# S284X.net
KiCad netlist of a schematic drawn in EAGLE
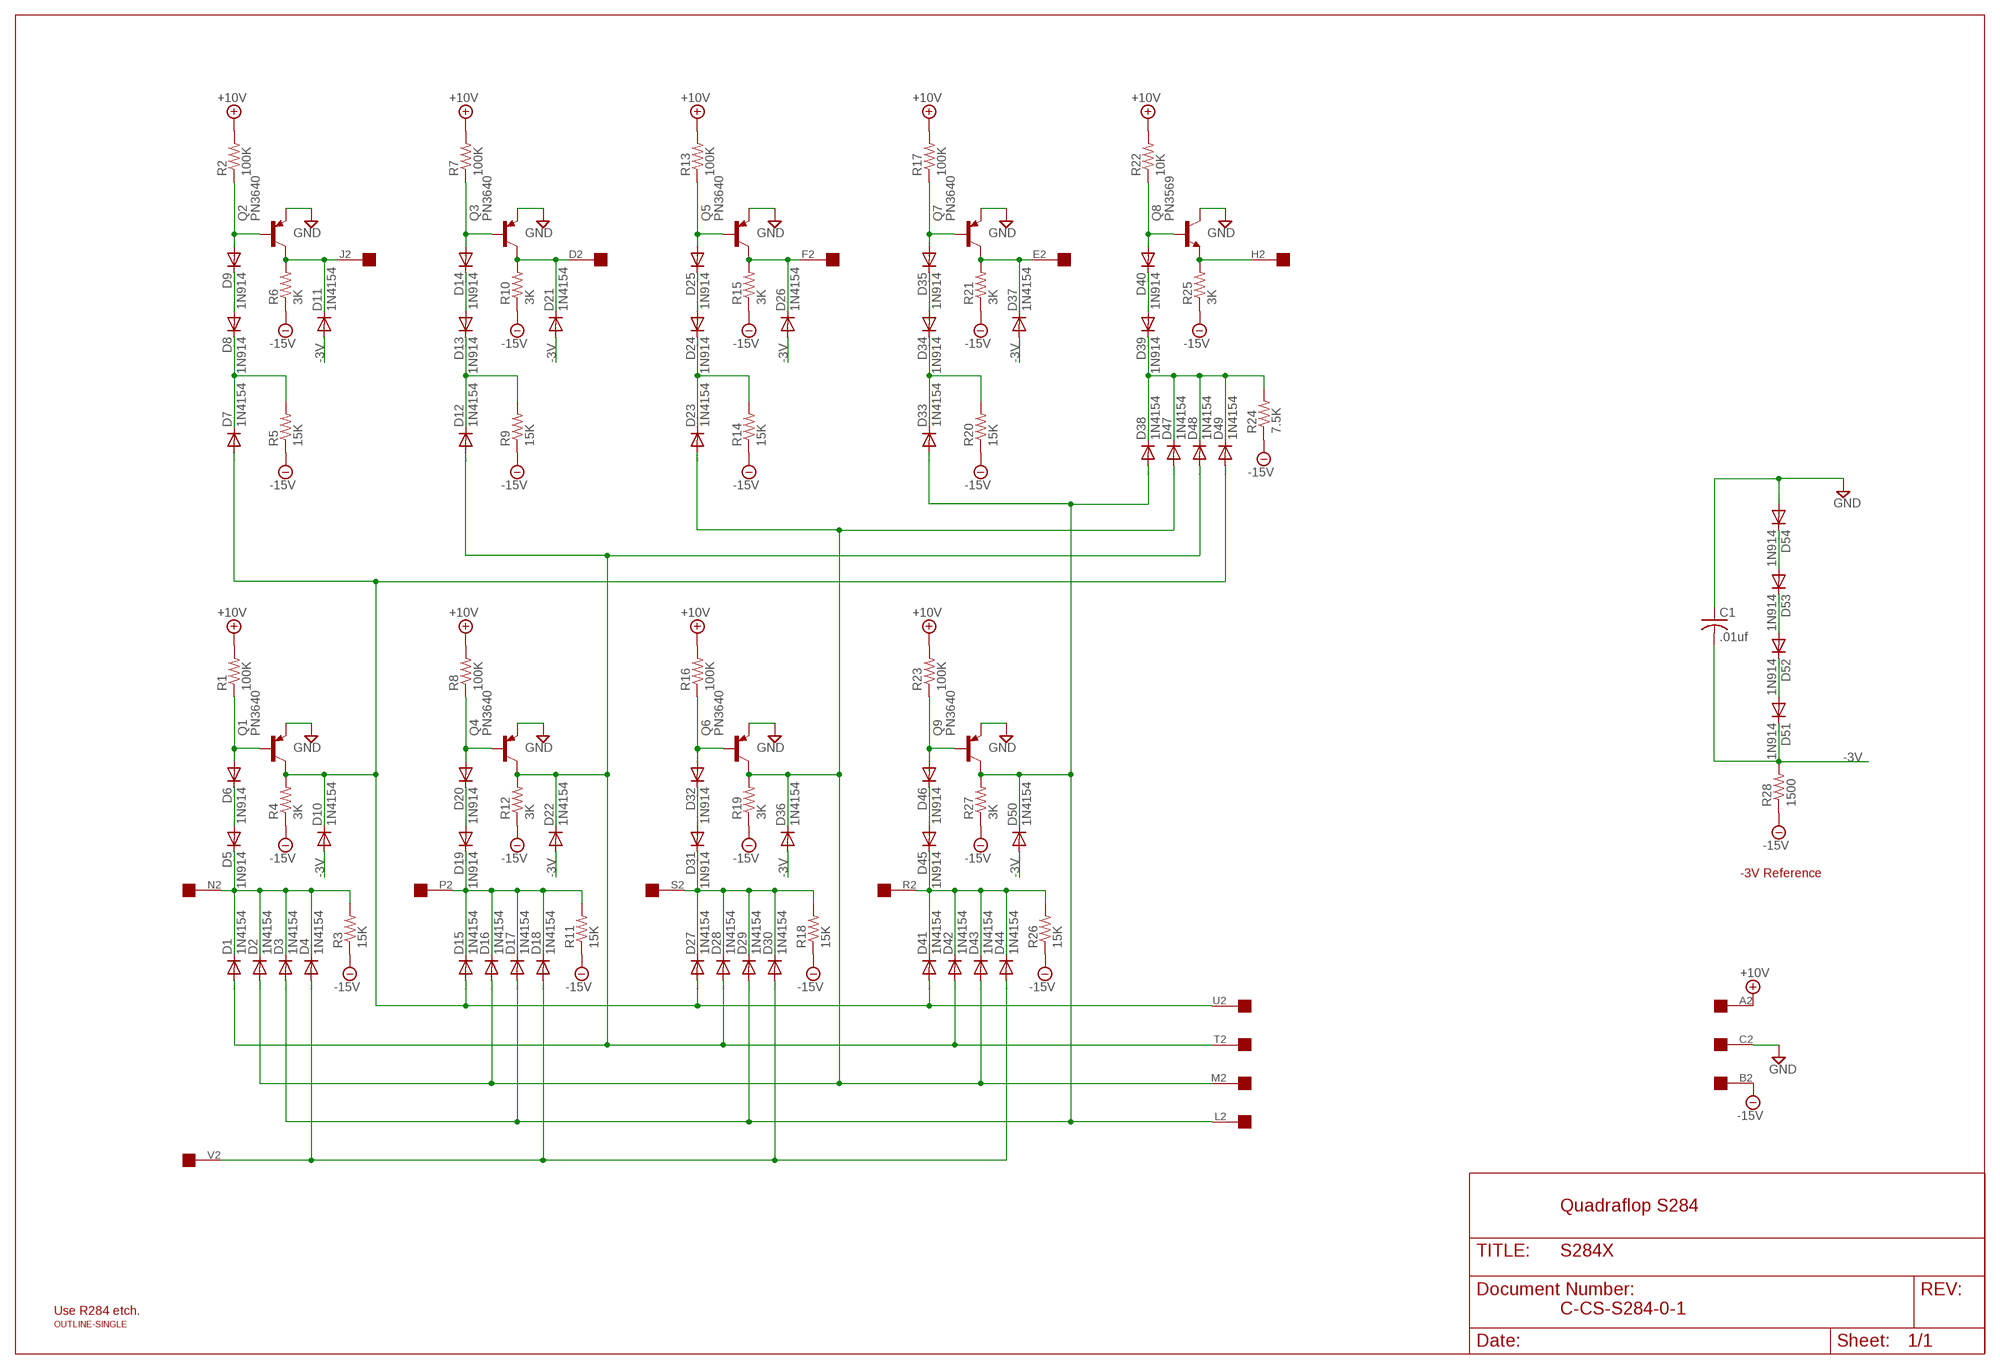
[diagram p0: schematic, sheet 1]

(export (version "E")
  (design (tool "Eeschema 10.0.6"))
  (components
    (comp (ref "C1")
      (value ".01uf")
      (footprint "eagle-import:C050-025X075")
      (libsource (lib "eagle-import") (part "C-US050-025X075"))
    )
    (comp (ref "D1")
      (value "1N4154")
      (footprint "eagle-import:DO35-10")
      (libsource (lib "eagle-import") (part "1N4148DO35-10"))
    )
    (comp (ref "D2")
      (value "1N4154")
      (footprint "eagle-import:DO35-10")
      (libsource (lib "eagle-import") (part "1N4148DO35-10"))
    )
    (comp (ref "D3")
      (value "1N4154")
      (footprint "eagle-import:DO35-10")
      (libsource (lib "eagle-import") (part "1N4148DO35-10"))
    )
    (comp (ref "D4")
      (value "1N4154")
      (footprint "eagle-import:DO35-10")
      (libsource (lib "eagle-import") (part "1N4148DO35-10"))
    )
    (comp (ref "D5")
      (value "1N914")
      (footprint "eagle-import:DO35-10")
      (libsource (lib "eagle-import") (part "1N4148DO35-10"))
    )
    (comp (ref "D6")
      (value "1N914")
      (footprint "eagle-import:DO35-10")
      (libsource (lib "eagle-import") (part "1N4148DO35-10"))
    )
    (comp (ref "D7")
      (value "1N4154")
      (footprint "eagle-import:DO35-10")
      (libsource (lib "eagle-import") (part "1N4148DO35-10"))
    )
    (comp (ref "D8")
      (value "1N914")
      (footprint "eagle-import:DO35-10")
      (libsource (lib "eagle-import") (part "1N4148DO35-10"))
    )
    (comp (ref "D9")
      (value "1N914")
      (footprint "eagle-import:DO35-10")
      (libsource (lib "eagle-import") (part "1N4148DO35-10"))
    )
    (comp (ref "D10")
      (value "1N4154")
      (footprint "eagle-import:DO35-10")
      (libsource (lib "eagle-import") (part "1N4148DO35-10"))
    )
    (comp (ref "D11")
      (value "1N4154")
      (footprint "eagle-import:DO35-10")
      (libsource (lib "eagle-import") (part "1N4148DO35-10"))
    )
    (comp (ref "D12")
      (value "1N4154")
      (footprint "eagle-import:DO35-10")
      (libsource (lib "eagle-import") (part "1N4148DO35-10"))
    )
    (comp (ref "D13")
      (value "1N914")
      (footprint "eagle-import:DO35-10")
      (libsource (lib "eagle-import") (part "1N4148DO35-10"))
    )
    (comp (ref "D14")
      (value "1N914")
      (footprint "eagle-import:DO35-10")
      (libsource (lib "eagle-import") (part "1N4148DO35-10"))
    )
    (comp (ref "D15")
      (value "1N4154")
      (footprint "eagle-import:DO35-10")
      (libsource (lib "eagle-import") (part "1N4148DO35-10"))
    )
    (comp (ref "D16")
      (value "1N4154")
      (footprint "eagle-import:DO35-10")
      (libsource (lib "eagle-import") (part "1N4148DO35-10"))
    )
    (comp (ref "D17")
      (value "1N4154")
      (footprint "eagle-import:DO35-10")
      (libsource (lib "eagle-import") (part "1N4148DO35-10"))
    )
    (comp (ref "D18")
      (value "1N4154")
      (footprint "eagle-import:DO35-10")
      (libsource (lib "eagle-import") (part "1N4148DO35-10"))
    )
    (comp (ref "D19")
      (value "1N914")
      (footprint "eagle-import:DO35-10")
      (libsource (lib "eagle-import") (part "1N4148DO35-10"))
    )
    (comp (ref "D20")
      (value "1N914")
      (footprint "eagle-import:DO35-10")
      (libsource (lib "eagle-import") (part "1N4148DO35-10"))
    )
    (comp (ref "D21")
      (value "1N4154")
      (footprint "eagle-import:DO35-10")
      (libsource (lib "eagle-import") (part "1N4148DO35-10"))
    )
    (comp (ref "D22")
      (value "1N4154")
      (footprint "eagle-import:DO35-10")
      (libsource (lib "eagle-import") (part "1N4148DO35-10"))
    )
    (comp (ref "D23")
      (value "1N4154")
      (footprint "eagle-import:DO35-10")
      (libsource (lib "eagle-import") (part "1N4148DO35-10"))
    )
    (comp (ref "D24")
      (value "1N914")
      (footprint "eagle-import:DO35-10")
      (libsource (lib "eagle-import") (part "1N4148DO35-10"))
    )
    (comp (ref "D25")
      (value "1N914")
      (footprint "eagle-import:DO35-10")
      (libsource (lib "eagle-import") (part "1N4148DO35-10"))
    )
    (comp (ref "D26")
      (value "1N4154")
      (footprint "eagle-import:DO35-10")
      (libsource (lib "eagle-import") (part "1N4148DO35-10"))
    )
    (comp (ref "D27")
      (value "1N4154")
      (footprint "eagle-import:DO35-10")
      (libsource (lib "eagle-import") (part "1N4148DO35-10"))
    )
    (comp (ref "D28")
      (value "1N4154")
      (footprint "eagle-import:DO35-10")
      (libsource (lib "eagle-import") (part "1N4148DO35-10"))
    )
    (comp (ref "D29")
      (value "1N4154")
      (footprint "eagle-import:DO35-10")
      (libsource (lib "eagle-import") (part "1N4148DO35-10"))
    )
    (comp (ref "D30")
      (value "1N4154")
      (footprint "eagle-import:DO35-10")
      (libsource (lib "eagle-import") (part "1N4148DO35-10"))
    )
    (comp (ref "D31")
      (value "1N914")
      (footprint "eagle-import:DO35-10")
      (libsource (lib "eagle-import") (part "1N4148DO35-10"))
    )
    (comp (ref "D32")
      (value "1N914")
      (footprint "eagle-import:DO35-10")
      (libsource (lib "eagle-import") (part "1N4148DO35-10"))
    )
    (comp (ref "D33")
      (value "1N4154")
      (footprint "eagle-import:DO35-10")
      (libsource (lib "eagle-import") (part "1N4148DO35-10"))
    )
    (comp (ref "D34")
      (value "1N914")
      (footprint "eagle-import:DO35-10")
      (libsource (lib "eagle-import") (part "1N4148DO35-10"))
    )
    (comp (ref "D35")
      (value "1N914")
      (footprint "eagle-import:DO35-10")
      (libsource (lib "eagle-import") (part "1N4148DO35-10"))
    )
    (comp (ref "D36")
      (value "1N4154")
      (footprint "eagle-import:DO35-10")
      (libsource (lib "eagle-import") (part "1N4148DO35-10"))
    )
    (comp (ref "D37")
      (value "1N4154")
      (footprint "eagle-import:DO35-10")
      (libsource (lib "eagle-import") (part "1N4148DO35-10"))
    )
    (comp (ref "D38")
      (value "1N4154")
      (footprint "eagle-import:DO35-10")
      (libsource (lib "eagle-import") (part "1N4148DO35-10"))
    )
    (comp (ref "D39")
      (value "1N914")
      (footprint "eagle-import:DO35-10")
      (libsource (lib "eagle-import") (part "1N4148DO35-10"))
    )
    (comp (ref "D40")
      (value "1N914")
      (footprint "eagle-import:DO35-10")
      (libsource (lib "eagle-import") (part "1N4148DO35-10"))
    )
    (comp (ref "D41")
      (value "1N4154")
      (footprint "eagle-import:DO35-10")
      (libsource (lib "eagle-import") (part "1N4148DO35-10"))
    )
    (comp (ref "D42")
      (value "1N4154")
      (footprint "eagle-import:DO35-10")
      (libsource (lib "eagle-import") (part "1N4148DO35-10"))
    )
    (comp (ref "D43")
      (value "1N4154")
      (footprint "eagle-import:DO35-10")
      (libsource (lib "eagle-import") (part "1N4148DO35-10"))
    )
    (comp (ref "D44")
      (value "1N4154")
      (footprint "eagle-import:DO35-10")
      (libsource (lib "eagle-import") (part "1N4148DO35-10"))
    )
    (comp (ref "D45")
      (value "1N914")
      (footprint "eagle-import:DO35-10")
      (libsource (lib "eagle-import") (part "1N4148DO35-10"))
    )
    (comp (ref "D46")
      (value "1N914")
      (footprint "eagle-import:DO35-10")
      (libsource (lib "eagle-import") (part "1N4148DO35-10"))
    )
    (comp (ref "D47")
      (value "1N4154")
      (footprint "eagle-import:DO35-10")
      (libsource (lib "eagle-import") (part "1N4148DO35-10"))
    )
    (comp (ref "D48")
      (value "1N4154")
      (footprint "eagle-import:DO35-10")
      (libsource (lib "eagle-import") (part "1N4148DO35-10"))
    )
    (comp (ref "D49")
      (value "1N4154")
      (footprint "eagle-import:DO35-10")
      (libsource (lib "eagle-import") (part "1N4148DO35-10"))
    )
    (comp (ref "D50")
      (value "1N4154")
      (footprint "eagle-import:DO35-10")
      (libsource (lib "eagle-import") (part "1N4148DO35-10"))
    )
    (comp (ref "D51")
      (value "1N914")
      (footprint "eagle-import:DO35-10")
      (libsource (lib "eagle-import") (part "1N4148DO35-10"))
    )
    (comp (ref "D52")
      (value "1N914")
      (footprint "eagle-import:DO35-10")
      (libsource (lib "eagle-import") (part "1N4148DO35-10"))
    )
    (comp (ref "D53")
      (value "1N914")
      (footprint "eagle-import:DO35-10")
      (libsource (lib "eagle-import") (part "1N4148DO35-10"))
    )
    (comp (ref "D54")
      (value "1N914")
      (footprint "eagle-import:DO35-10")
      (libsource (lib "eagle-import") (part "1N4148DO35-10"))
    )
    (comp (ref "Q1")
      (value "PN3640")
      (footprint "eagle-import:TO39")
      (libsource (lib "eagle-import") (part "2N3637"))
    )
    (comp (ref "Q2")
      (value "PN3640")
      (footprint "eagle-import:TO39")
      (libsource (lib "eagle-import") (part "2N3637"))
    )
    (comp (ref "Q3")
      (value "PN3640")
      (footprint "eagle-import:TO39")
      (libsource (lib "eagle-import") (part "2N3637"))
    )
    (comp (ref "Q4")
      (value "PN3640")
      (footprint "eagle-import:TO39")
      (libsource (lib "eagle-import") (part "2N3637"))
    )
    (comp (ref "Q5")
      (value "PN3640")
      (footprint "eagle-import:TO39")
      (libsource (lib "eagle-import") (part "2N3637"))
    )
    (comp (ref "Q6")
      (value "PN3640")
      (footprint "eagle-import:TO39")
      (libsource (lib "eagle-import") (part "2N3637"))
    )
    (comp (ref "Q7")
      (value "PN3640")
      (footprint "eagle-import:TO39")
      (libsource (lib "eagle-import") (part "2N3637"))
    )
    (comp (ref "Q8")
      (value "PN3569")
      (footprint "eagle-import:TO5")
      (libsource (lib "eagle-import") (part "2N2102"))
    )
    (comp (ref "Q9")
      (value "PN3640")
      (footprint "eagle-import:TO39")
      (libsource (lib "eagle-import") (part "2N3637"))
    )
    (comp (ref "R1")
      (value "100K")
      (footprint "eagle-import:0207_10")
      (libsource (lib "eagle-import") (part "R-US_0207/10"))
    )
    (comp (ref "R2")
      (value "100K")
      (footprint "eagle-import:0207_10")
      (libsource (lib "eagle-import") (part "R-US_0207/10"))
    )
    (comp (ref "R3")
      (value "15K")
      (footprint "eagle-import:0207_10")
      (libsource (lib "eagle-import") (part "R-US_0207/10"))
    )
    (comp (ref "R4")
      (value "3K")
      (footprint "eagle-import:0207_10")
      (libsource (lib "eagle-import") (part "R-US_0207/10"))
    )
    (comp (ref "R5")
      (value "15K")
      (footprint "eagle-import:0207_10")
      (libsource (lib "eagle-import") (part "R-US_0207/10"))
    )
    (comp (ref "R6")
      (value "3K")
      (footprint "eagle-import:0207_10")
      (libsource (lib "eagle-import") (part "R-US_0207/10"))
    )
    (comp (ref "R7")
      (value "100K")
      (footprint "eagle-import:0207_10")
      (libsource (lib "eagle-import") (part "R-US_0207/10"))
    )
    (comp (ref "R8")
      (value "100K")
      (footprint "eagle-import:0207_10")
      (libsource (lib "eagle-import") (part "R-US_0207/10"))
    )
    (comp (ref "R9")
      (value "15K")
      (footprint "eagle-import:0207_10")
      (libsource (lib "eagle-import") (part "R-US_0207/10"))
    )
    (comp (ref "R10")
      (value "3K")
      (footprint "eagle-import:0207_10")
      (libsource (lib "eagle-import") (part "R-US_0207/10"))
    )
    (comp (ref "R11")
      (value "15K")
      (footprint "eagle-import:0207_10")
      (libsource (lib "eagle-import") (part "R-US_0207/10"))
    )
    (comp (ref "R12")
      (value "3K")
      (footprint "eagle-import:0207_10")
      (libsource (lib "eagle-import") (part "R-US_0207/10"))
    )
    (comp (ref "R13")
      (value "100K")
      (footprint "eagle-import:0207_10")
      (libsource (lib "eagle-import") (part "R-US_0207/10"))
    )
    (comp (ref "R14")
      (value "15K")
      (footprint "eagle-import:0207_10")
      (libsource (lib "eagle-import") (part "R-US_0207/10"))
    )
    (comp (ref "R15")
      (value "3K")
      (footprint "eagle-import:0207_10")
      (libsource (lib "eagle-import") (part "R-US_0207/10"))
    )
    (comp (ref "R16")
      (value "100K")
      (footprint "eagle-import:0207_10")
      (libsource (lib "eagle-import") (part "R-US_0207/10"))
    )
    (comp (ref "R17")
      (value "100K")
      (footprint "eagle-import:0207_10")
      (libsource (lib "eagle-import") (part "R-US_0207/10"))
    )
    (comp (ref "R18")
      (value "15K")
      (footprint "eagle-import:0207_10")
      (libsource (lib "eagle-import") (part "R-US_0207/10"))
    )
    (comp (ref "R19")
      (value "3K")
      (footprint "eagle-import:0207_10")
      (libsource (lib "eagle-import") (part "R-US_0207/10"))
    )
    (comp (ref "R20")
      (value "15K")
      (footprint "eagle-import:0207_10")
      (libsource (lib "eagle-import") (part "R-US_0207/10"))
    )
    (comp (ref "R21")
      (value "3K")
      (footprint "eagle-import:0207_10")
      (libsource (lib "eagle-import") (part "R-US_0207/10"))
    )
    (comp (ref "R22")
      (value "10K")
      (footprint "eagle-import:0207_10")
      (libsource (lib "eagle-import") (part "R-US_0207/10"))
    )
    (comp (ref "R23")
      (value "100K")
      (footprint "eagle-import:0207_10")
      (libsource (lib "eagle-import") (part "R-US_0207/10"))
    )
    (comp (ref "R24")
      (value "7.5K")
      (footprint "eagle-import:0207_10")
      (libsource (lib "eagle-import") (part "R-US_0207/10"))
    )
    (comp (ref "R25")
      (value "3K")
      (footprint "eagle-import:0207_10")
      (libsource (lib "eagle-import") (part "R-US_0207/10"))
    )
    (comp (ref "R26")
      (value "15K")
      (footprint "eagle-import:0207_10")
      (libsource (lib "eagle-import") (part "R-US_0207/10"))
    )
    (comp (ref "R27")
      (value "3K")
      (footprint "eagle-import:0207_10")
      (libsource (lib "eagle-import") (part "R-US_0207/10"))
    )
    (comp (ref "R28")
      (value "1500")
      (footprint "eagle-import:0207_10")
      (libsource (lib "eagle-import") (part "R-US_0207/10"))
    )
    (comp (ref "U$1")
      (value "OUTLINE-SINGLE")
      (footprint "eagle-import:SINGLE")
      (libsource (lib "eagle-import") (part "OUTLINE-SINGLE"))
    )
    (comp (ref "U$2")
      (value "EDGE-1")
      (footprint "eagle-import:EDGE-CON1")
      (libsource (lib "eagle-import") (part "EDGE-1"))
    )
  )
  (nets
    (net (code "1") (name "+10V") (class "Default")
      (node (ref "R1") (pin "2") (pinfunction "2_2") (pintype "passive"))
      (node (ref "R13") (pin "2") (pinfunction "2_2") (pintype "passive"))
      (node (ref "R16") (pin "2") (pinfunction "2_2") (pintype "passive"))
      (node (ref "R17") (pin "2") (pinfunction "2_2") (pintype "passive"))
      (node (ref "R2") (pin "2") (pinfunction "2_2") (pintype "passive"))
      (node (ref "R22") (pin "2") (pinfunction "2_2") (pintype "passive"))
      (node (ref "R23") (pin "2") (pinfunction "2_2") (pintype "passive"))
      (node (ref "R7") (pin "2") (pinfunction "2_2") (pintype "passive"))
      (node (ref "R8") (pin "2") (pinfunction "2_2") (pintype "passive"))
      (node (ref "U$2") (pin "A2") (pinfunction "1_A2") (pintype "bidirectional"))
    )
    (net (code "2") (name "-15V") (class "Default")
      (node (ref "R10") (pin "1") (pinfunction "1_1") (pintype "passive"))
      (node (ref "R11") (pin "1") (pinfunction "1_1") (pintype "passive"))
      (node (ref "R12") (pin "1") (pinfunction "1_1") (pintype "passive"))
      (node (ref "R14") (pin "1") (pinfunction "1_1") (pintype "passive"))
      (node (ref "R15") (pin "1") (pinfunction "1_1") (pintype "passive"))
      (node (ref "R18") (pin "1") (pinfunction "1_1") (pintype "passive"))
      (node (ref "R19") (pin "1") (pinfunction "1_1") (pintype "passive"))
      (node (ref "R20") (pin "1") (pinfunction "1_1") (pintype "passive"))
      (node (ref "R21") (pin "1") (pinfunction "1_1") (pintype "passive"))
      (node (ref "R24") (pin "1") (pinfunction "1_1") (pintype "passive"))
      (node (ref "R25") (pin "1") (pinfunction "1_1") (pintype "passive"))
      (node (ref "R26") (pin "1") (pinfunction "1_1") (pintype "passive"))
      (node (ref "R27") (pin "1") (pinfunction "1_1") (pintype "passive"))
      (node (ref "R28") (pin "1") (pinfunction "1_1") (pintype "passive"))
      (node (ref "R3") (pin "1") (pinfunction "1_1") (pintype "passive"))
      (node (ref "R4") (pin "1") (pinfunction "1_1") (pintype "passive"))
      (node (ref "R5") (pin "1") (pinfunction "1_1") (pintype "passive"))
      (node (ref "R6") (pin "1") (pinfunction "1_1") (pintype "passive"))
      (node (ref "R9") (pin "1") (pinfunction "1_1") (pintype "passive"))
      (node (ref "U$2") (pin "B2") (pinfunction "1_B2") (pintype "bidirectional"))
    )
    (net (code "3") (name "/-3V") (class "Default")
      (node (ref "C1") (pin "2") (pinfunction "2_2") (pintype "passive"))
      (node (ref "D10") (pin "A") (pinfunction "A_A") (pintype "passive"))
      (node (ref "D11") (pin "A") (pinfunction "A_A") (pintype "passive"))
      (node (ref "D21") (pin "A") (pinfunction "A_A") (pintype "passive"))
      (node (ref "D22") (pin "A") (pinfunction "A_A") (pintype "passive"))
      (node (ref "D26") (pin "A") (pinfunction "A_A") (pintype "passive"))
      (node (ref "D36") (pin "A") (pinfunction "A_A") (pintype "passive"))
      (node (ref "D37") (pin "A") (pinfunction "A_A") (pintype "passive"))
      (node (ref "D50") (pin "A") (pinfunction "A_A") (pintype "passive"))
      (node (ref "D51") (pin "C") (pinfunction "C_C") (pintype "passive"))
      (node (ref "R28") (pin "2") (pinfunction "2_2") (pintype "passive"))
    )
    (net (code "4") (name "GND") (class "Default")
      (node (ref "C1") (pin "1") (pinfunction "1_1") (pintype "passive"))
      (node (ref "D54") (pin "A") (pinfunction "A_A") (pintype "passive"))
      (node (ref "Q1") (pin "1") (pinfunction "E_1") (pintype "passive"))
      (node (ref "Q2") (pin "1") (pinfunction "E_1") (pintype "passive"))
      (node (ref "Q3") (pin "1") (pinfunction "E_1") (pintype "passive"))
      (node (ref "Q4") (pin "1") (pinfunction "E_1") (pintype "passive"))
      (node (ref "Q5") (pin "1") (pinfunction "E_1") (pintype "passive"))
      (node (ref "Q6") (pin "1") (pinfunction "E_1") (pintype "passive"))
      (node (ref "Q7") (pin "1") (pinfunction "E_1") (pintype "passive"))
      (node (ref "Q8") (pin "3") (pinfunction "C_3") (pintype "passive"))
      (node (ref "Q9") (pin "1") (pinfunction "E_1") (pintype "passive"))
      (node (ref "U$2") (pin "C2") (pinfunction "1_C2") (pintype "bidirectional"))
    )
    (net (code "5") (name "Net-(D5-PadA)") (class "Default")
      (node (ref "D5") (pin "A") (pinfunction "A_A") (pintype "passive"))
      (node (ref "D6") (pin "C") (pinfunction "C_C") (pintype "passive"))
    )
    (net (code "6") (name "Net-(D7-PadC)") (class "Default")
      (node (ref "D7") (pin "C") (pinfunction "C_C") (pintype "passive"))
      (node (ref "D8") (pin "C") (pinfunction "C_C") (pintype "passive"))
      (node (ref "R5") (pin "2") (pinfunction "2_2") (pintype "passive"))
    )
    (net (code "7") (name "Net-(D8-PadA)") (class "Default")
      (node (ref "D8") (pin "A") (pinfunction "A_A") (pintype "passive"))
      (node (ref "D9") (pin "C") (pinfunction "C_C") (pintype "passive"))
    )
    (net (code "8") (name "Net-(D12-PadC)") (class "Default")
      (node (ref "D12") (pin "C") (pinfunction "C_C") (pintype "passive"))
      (node (ref "D13") (pin "C") (pinfunction "C_C") (pintype "passive"))
      (node (ref "R9") (pin "2") (pinfunction "2_2") (pintype "passive"))
    )
    (net (code "9") (name "Net-(D13-PadA)") (class "Default")
      (node (ref "D13") (pin "A") (pinfunction "A_A") (pintype "passive"))
      (node (ref "D14") (pin "C") (pinfunction "C_C") (pintype "passive"))
    )
    (net (code "10") (name "Net-(D19-PadA)") (class "Default")
      (node (ref "D19") (pin "A") (pinfunction "A_A") (pintype "passive"))
      (node (ref "D20") (pin "C") (pinfunction "C_C") (pintype "passive"))
    )
    (net (code "11") (name "Net-(D23-PadC)") (class "Default")
      (node (ref "D23") (pin "C") (pinfunction "C_C") (pintype "passive"))
      (node (ref "D24") (pin "C") (pinfunction "C_C") (pintype "passive"))
      (node (ref "R14") (pin "2") (pinfunction "2_2") (pintype "passive"))
    )
    (net (code "12") (name "Net-(D24-PadA)") (class "Default")
      (node (ref "D24") (pin "A") (pinfunction "A_A") (pintype "passive"))
      (node (ref "D25") (pin "C") (pinfunction "C_C") (pintype "passive"))
    )
    (net (code "13") (name "Net-(D31-PadA)") (class "Default")
      (node (ref "D31") (pin "A") (pinfunction "A_A") (pintype "passive"))
      (node (ref "D32") (pin "C") (pinfunction "C_C") (pintype "passive"))
    )
    (net (code "14") (name "Net-(D33-PadC)") (class "Default")
      (node (ref "D33") (pin "C") (pinfunction "C_C") (pintype "passive"))
      (node (ref "D34") (pin "C") (pinfunction "C_C") (pintype "passive"))
      (node (ref "R20") (pin "2") (pinfunction "2_2") (pintype "passive"))
    )
    (net (code "15") (name "Net-(D34-PadA)") (class "Default")
      (node (ref "D34") (pin "A") (pinfunction "A_A") (pintype "passive"))
      (node (ref "D35") (pin "C") (pinfunction "C_C") (pintype "passive"))
    )
    (net (code "16") (name "Net-(D38-PadC)") (class "Default")
      (node (ref "D38") (pin "C") (pinfunction "C_C") (pintype "passive"))
      (node (ref "D39") (pin "C") (pinfunction "C_C") (pintype "passive"))
      (node (ref "D47") (pin "C") (pinfunction "C_C") (pintype "passive"))
      (node (ref "D48") (pin "C") (pinfunction "C_C") (pintype "passive"))
      (node (ref "D49") (pin "C") (pinfunction "C_C") (pintype "passive"))
      (node (ref "R24") (pin "2") (pinfunction "2_2") (pintype "passive"))
    )
    (net (code "17") (name "Net-(D39-PadA)") (class "Default")
      (node (ref "D39") (pin "A") (pinfunction "A_A") (pintype "passive"))
      (node (ref "D40") (pin "C") (pinfunction "C_C") (pintype "passive"))
    )
    (net (code "18") (name "Net-(D45-PadA)") (class "Default")
      (node (ref "D45") (pin "A") (pinfunction "A_A") (pintype "passive"))
      (node (ref "D46") (pin "C") (pinfunction "C_C") (pintype "passive"))
    )
    (net (code "19") (name "Net-(D51-PadA)") (class "Default")
      (node (ref "D51") (pin "A") (pinfunction "A_A") (pintype "passive"))
      (node (ref "D52") (pin "C") (pinfunction "C_C") (pintype "passive"))
    )
    (net (code "20") (name "Net-(D52-PadA)") (class "Default")
      (node (ref "D52") (pin "A") (pinfunction "A_A") (pintype "passive"))
      (node (ref "D53") (pin "C") (pinfunction "C_C") (pintype "passive"))
    )
    (net (code "21") (name "Net-(D53-PadA)") (class "Default")
      (node (ref "D53") (pin "A") (pinfunction "A_A") (pintype "passive"))
      (node (ref "D54") (pin "C") (pinfunction "C_C") (pintype "passive"))
    )
    (net (code "22") (name "Net-(Q1-B)") (class "Default")
      (node (ref "D6") (pin "A") (pinfunction "A_A") (pintype "passive"))
      (node (ref "Q1") (pin "2") (pinfunction "B_2") (pintype "passive"))
      (node (ref "R1") (pin "1") (pinfunction "1_1") (pintype "passive"))
    )
    (net (code "23") (name "Net-(Q1-C)") (class "Default")
      (node (ref "D10") (pin "C") (pinfunction "C_C") (pintype "passive"))
      (node (ref "D15") (pin "A") (pinfunction "A_A") (pintype "passive"))
      (node (ref "D27") (pin "A") (pinfunction "A_A") (pintype "passive"))
      (node (ref "D41") (pin "A") (pinfunction "A_A") (pintype "passive"))
      (node (ref "D49") (pin "A") (pinfunction "A_A") (pintype "passive"))
      (node (ref "D7") (pin "A") (pinfunction "A_A") (pintype "passive"))
      (node (ref "Q1") (pin "3") (pinfunction "C_3") (pintype "passive"))
      (node (ref "R4") (pin "2") (pinfunction "2_2") (pintype "passive"))
      (node (ref "U$2") (pin "U2") (pinfunction "1_U2") (pintype "bidirectional"))
    )
    (net (code "24") (name "Net-(Q2-B)") (class "Default")
      (node (ref "D9") (pin "A") (pinfunction "A_A") (pintype "passive"))
      (node (ref "Q2") (pin "2") (pinfunction "B_2") (pintype "passive"))
      (node (ref "R2") (pin "1") (pinfunction "1_1") (pintype "passive"))
    )
    (net (code "25") (name "Net-(Q2-C)") (class "Default")
      (node (ref "D11") (pin "C") (pinfunction "C_C") (pintype "passive"))
      (node (ref "Q2") (pin "3") (pinfunction "C_3") (pintype "passive"))
      (node (ref "R6") (pin "2") (pinfunction "2_2") (pintype "passive"))
      (node (ref "U$2") (pin "J2") (pinfunction "1_J2") (pintype "bidirectional"))
    )
    (net (code "26") (name "Net-(Q3-B)") (class "Default")
      (node (ref "D14") (pin "A") (pinfunction "A_A") (pintype "passive"))
      (node (ref "Q3") (pin "2") (pinfunction "B_2") (pintype "passive"))
      (node (ref "R7") (pin "1") (pinfunction "1_1") (pintype "passive"))
    )
    (net (code "27") (name "Net-(Q3-C)") (class "Default")
      (node (ref "D21") (pin "C") (pinfunction "C_C") (pintype "passive"))
      (node (ref "Q3") (pin "3") (pinfunction "C_3") (pintype "passive"))
      (node (ref "R10") (pin "2") (pinfunction "2_2") (pintype "passive"))
      (node (ref "U$2") (pin "D2") (pinfunction "1_D2") (pintype "bidirectional"))
    )
    (net (code "28") (name "Net-(Q4-B)") (class "Default")
      (node (ref "D20") (pin "A") (pinfunction "A_A") (pintype "passive"))
      (node (ref "Q4") (pin "2") (pinfunction "B_2") (pintype "passive"))
      (node (ref "R8") (pin "1") (pinfunction "1_1") (pintype "passive"))
    )
    (net (code "29") (name "Net-(Q4-C)") (class "Default")
      (node (ref "D1") (pin "A") (pinfunction "A_A") (pintype "passive"))
      (node (ref "D12") (pin "A") (pinfunction "A_A") (pintype "passive"))
      (node (ref "D22") (pin "C") (pinfunction "C_C") (pintype "passive"))
      (node (ref "D28") (pin "A") (pinfunction "A_A") (pintype "passive"))
      (node (ref "D42") (pin "A") (pinfunction "A_A") (pintype "passive"))
      (node (ref "D48") (pin "A") (pinfunction "A_A") (pintype "passive"))
      (node (ref "Q4") (pin "3") (pinfunction "C_3") (pintype "passive"))
      (node (ref "R12") (pin "2") (pinfunction "2_2") (pintype "passive"))
      (node (ref "U$2") (pin "T2") (pinfunction "1_T2") (pintype "bidirectional"))
    )
    (net (code "30") (name "Net-(Q5-B)") (class "Default")
      (node (ref "D25") (pin "A") (pinfunction "A_A") (pintype "passive"))
      (node (ref "Q5") (pin "2") (pinfunction "B_2") (pintype "passive"))
      (node (ref "R13") (pin "1") (pinfunction "1_1") (pintype "passive"))
    )
    (net (code "31") (name "Net-(Q5-C)") (class "Default")
      (node (ref "D26") (pin "C") (pinfunction "C_C") (pintype "passive"))
      (node (ref "Q5") (pin "3") (pinfunction "C_3") (pintype "passive"))
      (node (ref "R15") (pin "2") (pinfunction "2_2") (pintype "passive"))
      (node (ref "U$2") (pin "F2") (pinfunction "1_F2") (pintype "bidirectional"))
    )
    (net (code "32") (name "Net-(Q6-B)") (class "Default")
      (node (ref "D32") (pin "A") (pinfunction "A_A") (pintype "passive"))
      (node (ref "Q6") (pin "2") (pinfunction "B_2") (pintype "passive"))
      (node (ref "R16") (pin "1") (pinfunction "1_1") (pintype "passive"))
    )
    (net (code "33") (name "Net-(Q6-C)") (class "Default")
      (node (ref "D16") (pin "A") (pinfunction "A_A") (pintype "passive"))
      (node (ref "D2") (pin "A") (pinfunction "A_A") (pintype "passive"))
      (node (ref "D23") (pin "A") (pinfunction "A_A") (pintype "passive"))
      (node (ref "D36") (pin "C") (pinfunction "C_C") (pintype "passive"))
      (node (ref "D43") (pin "A") (pinfunction "A_A") (pintype "passive"))
      (node (ref "D47") (pin "A") (pinfunction "A_A") (pintype "passive"))
      (node (ref "Q6") (pin "3") (pinfunction "C_3") (pintype "passive"))
      (node (ref "R19") (pin "2") (pinfunction "2_2") (pintype "passive"))
      (node (ref "U$2") (pin "M2") (pinfunction "1_M2") (pintype "bidirectional"))
    )
    (net (code "34") (name "Net-(Q7-B)") (class "Default")
      (node (ref "D35") (pin "A") (pinfunction "A_A") (pintype "passive"))
      (node (ref "Q7") (pin "2") (pinfunction "B_2") (pintype "passive"))
      (node (ref "R17") (pin "1") (pinfunction "1_1") (pintype "passive"))
    )
    (net (code "35") (name "Net-(Q7-C)") (class "Default")
      (node (ref "D37") (pin "C") (pinfunction "C_C") (pintype "passive"))
      (node (ref "Q7") (pin "3") (pinfunction "C_3") (pintype "passive"))
      (node (ref "R21") (pin "2") (pinfunction "2_2") (pintype "passive"))
      (node (ref "U$2") (pin "E2") (pinfunction "1_E2") (pintype "bidirectional"))
    )
    (net (code "36") (name "Net-(Q8-B)") (class "Default")
      (node (ref "D40") (pin "A") (pinfunction "A_A") (pintype "passive"))
      (node (ref "Q8") (pin "2") (pinfunction "B_2") (pintype "passive"))
      (node (ref "R22") (pin "1") (pinfunction "1_1") (pintype "passive"))
    )
    (net (code "37") (name "Net-(Q8-E)") (class "Default")
      (node (ref "Q8") (pin "1") (pinfunction "E_1") (pintype "passive"))
      (node (ref "R25") (pin "2") (pinfunction "2_2") (pintype "passive"))
      (node (ref "U$2") (pin "H2") (pinfunction "1_H2") (pintype "bidirectional"))
    )
    (net (code "38") (name "Net-(Q9-B)") (class "Default")
      (node (ref "D46") (pin "A") (pinfunction "A_A") (pintype "passive"))
      (node (ref "Q9") (pin "2") (pinfunction "B_2") (pintype "passive"))
      (node (ref "R23") (pin "1") (pinfunction "1_1") (pintype "passive"))
    )
    (net (code "39") (name "Net-(Q9-C)") (class "Default")
      (node (ref "D17") (pin "A") (pinfunction "A_A") (pintype "passive"))
      (node (ref "D29") (pin "A") (pinfunction "A_A") (pintype "passive"))
      (node (ref "D3") (pin "A") (pinfunction "A_A") (pintype "passive"))
      (node (ref "D33") (pin "A") (pinfunction "A_A") (pintype "passive"))
      (node (ref "D38") (pin "A") (pinfunction "A_A") (pintype "passive"))
      (node (ref "D50") (pin "C") (pinfunction "C_C") (pintype "passive"))
      (node (ref "Q9") (pin "3") (pinfunction "C_3") (pintype "passive"))
      (node (ref "R27") (pin "2") (pinfunction "2_2") (pintype "passive"))
      (node (ref "U$2") (pin "L2") (pinfunction "1_L2") (pintype "bidirectional"))
    )
    (net (code "40") (name "Net-(U$2L-1)") (class "Default")
      (node (ref "D1") (pin "C") (pinfunction "C_C") (pintype "passive"))
      (node (ref "D2") (pin "C") (pinfunction "C_C") (pintype "passive"))
      (node (ref "D3") (pin "C") (pinfunction "C_C") (pintype "passive"))
      (node (ref "D4") (pin "C") (pinfunction "C_C") (pintype "passive"))
      (node (ref "D5") (pin "C") (pinfunction "C_C") (pintype "passive"))
      (node (ref "R3") (pin "2") (pinfunction "2_2") (pintype "passive"))
      (node (ref "U$2") (pin "N2") (pinfunction "1_N2") (pintype "bidirectional"))
    )
    (net (code "41") (name "Net-(U$2M-1)") (class "Default")
      (node (ref "D15") (pin "C") (pinfunction "C_C") (pintype "passive"))
      (node (ref "D16") (pin "C") (pinfunction "C_C") (pintype "passive"))
      (node (ref "D17") (pin "C") (pinfunction "C_C") (pintype "passive"))
      (node (ref "D18") (pin "C") (pinfunction "C_C") (pintype "passive"))
      (node (ref "D19") (pin "C") (pinfunction "C_C") (pintype "passive"))
      (node (ref "R11") (pin "2") (pinfunction "2_2") (pintype "passive"))
      (node (ref "U$2") (pin "P2") (pinfunction "1_P2") (pintype "bidirectional"))
    )
    (net (code "42") (name "Net-(U$2N-1)") (class "Default")
      (node (ref "D41") (pin "C") (pinfunction "C_C") (pintype "passive"))
      (node (ref "D42") (pin "C") (pinfunction "C_C") (pintype "passive"))
      (node (ref "D43") (pin "C") (pinfunction "C_C") (pintype "passive"))
      (node (ref "D44") (pin "C") (pinfunction "C_C") (pintype "passive"))
      (node (ref "D45") (pin "C") (pinfunction "C_C") (pintype "passive"))
      (node (ref "R26") (pin "2") (pinfunction "2_2") (pintype "passive"))
      (node (ref "U$2") (pin "R2") (pinfunction "1_R2") (pintype "bidirectional"))
    )
    (net (code "43") (name "Net-(U$2O-1)") (class "Default")
      (node (ref "D27") (pin "C") (pinfunction "C_C") (pintype "passive"))
      (node (ref "D28") (pin "C") (pinfunction "C_C") (pintype "passive"))
      (node (ref "D29") (pin "C") (pinfunction "C_C") (pintype "passive"))
      (node (ref "D30") (pin "C") (pinfunction "C_C") (pintype "passive"))
      (node (ref "D31") (pin "C") (pinfunction "C_C") (pintype "passive"))
      (node (ref "R18") (pin "2") (pinfunction "2_2") (pintype "passive"))
      (node (ref "U$2") (pin "S2") (pinfunction "1_S2") (pintype "bidirectional"))
    )
    (net (code "44") (name "Net-(U$2R-1)") (class "Default")
      (node (ref "D18") (pin "A") (pinfunction "A_A") (pintype "passive"))
      (node (ref "D30") (pin "A") (pinfunction "A_A") (pintype "passive"))
      (node (ref "D4") (pin "A") (pinfunction "A_A") (pintype "passive"))
      (node (ref "D44") (pin "A") (pinfunction "A_A") (pintype "passive"))
      (node (ref "U$2") (pin "V2") (pinfunction "1_V2") (pintype "bidirectional"))
    )
  )
)
